# 8_-Interface_RS485.net
KiCad netlist of a schematic drawn in Altium Designer
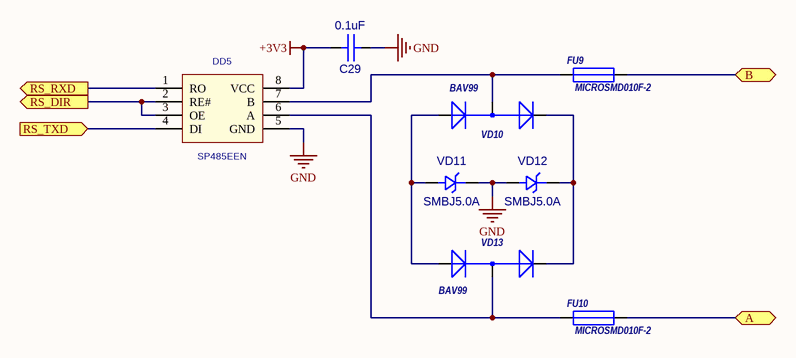
[diagram p0: [8]-Interface_RS485.SchDoc]

(export (version "E")
  (design (tool "Eeschema 10.0.6"))
  (components
    (comp (ref "C29")
      (value "0.1uF")
      (footprint "CC0603")
      (description "CC0603")
      (libsource (lib "gprs_modem_2") (part "CC0603"))
    )
    (comp (ref "DD5")
      (value "SP485EEN")
      (footprint "SO-8")
      (description "SP485")
      (libsource (lib "gprs_modem_2") (part "SP485"))
    )
    (comp (ref "FU9")
      (value "MICROSMD010F-2")
      (footprint "RC1210")
      (description "MICROSMD")
      (libsource (lib "gprs_modem_2") (part "MICROSMD"))
    )
    (comp (ref "FU10")
      (value "MICROSMD010F-2")
      (footprint "RC1210")
      (description "MICROSMD")
      (libsource (lib "gprs_modem_2") (part "MICROSMD"))
    )
    (comp (ref "VD10")
      (value "BAV99")
      (footprint "SOT-23(GSD)")
      (description "1.0 Ampere General Purpose Rectifier")
      (libsource (lib "gprs_modem_2") (part "BAV99"))
    )
    (comp (ref "VD11")
      (value "SMBJ5.0A")
      (footprint "SMB")
      (description "SMBJ")
      (libsource (lib "gprs_modem_2") (part "SMBJ"))
    )
    (comp (ref "VD12")
      (value "SMBJ5.0A")
      (footprint "SMB")
      (description "SMBJ")
      (libsource (lib "gprs_modem_2") (part "SMBJ"))
    )
    (comp (ref "VD13")
      (value "BAV99")
      (footprint "SOT-23(GSD)")
      (description "1.0 Ampere General Purpose Rectifier")
      (libsource (lib "gprs_modem_2") (part "BAV99"))
    )
  )
  (nets
    (net (code "1") (name "+3V3") (class "Default")
      (node (ref "C29") (pin "2") (pinfunction "B_2") (pintype "passive"))
      (node (ref "DD5") (pin "8") (pinfunction "VCC_8") (pintype "passive"))
    )
    (net (code "2") (name "/A") (class "Default") (node (ref "FU10") (pin "2") (pintype "passive")))
    (net (code "3") (name "/B") (class "Default") (node (ref "FU9") (pin "2") (pintype "passive")))
    (net (code "4") (name "/RS_DIR") (class "Default")
      (node (ref "DD5") (pin "2") (pinfunction "RE#_2") (pintype "passive"))
      (node (ref "DD5") (pin "3") (pinfunction "OE_3") (pintype "passive"))
    )
    (net (code "5") (name "/RS_RXD") (class "Default")
      (node (ref "DD5") (pin "1") (pinfunction "RO_1") (pintype "passive"))
    )
    (net (code "6") (name "/RS_TXD") (class "Default")
      (node (ref "DD5") (pin "4") (pinfunction "DI_4") (pintype "passive"))
    )
    (net (code "7") (name "GND") (class "Default")
      (node (ref "C29") (pin "1") (pinfunction "A_1") (pintype "passive"))
      (node (ref "DD5") (pin "5") (pinfunction "GND_5") (pintype "passive"))
      (node (ref "VD11") (pin "2") (pinfunction "K_2") (pintype "passive"))
      (node (ref "VD12") (pin "1") (pinfunction "A_1") (pintype "passive"))
    )
    (net (code "8") (name "Net-(DD5-A)") (class "Default")
      (node (ref "DD5") (pin "6") (pinfunction "A_6") (pintype "passive"))
      (node (ref "FU10") (pin "1") (pintype "passive"))
      (node (ref "VD13") (pin "3") (pinfunction "AK_3") (pintype "passive"))
    )
    (net (code "9") (name "Net-(DD5-B)") (class "Default")
      (node (ref "DD5") (pin "7") (pinfunction "B_7") (pintype "passive"))
      (node (ref "FU9") (pin "1") (pintype "passive"))
      (node (ref "VD10") (pin "3") (pinfunction "AK_3") (pintype "passive"))
    )
    (net (code "10") (name "Net-(VD10-A)") (class "Default")
      (node (ref "VD10") (pin "1") (pinfunction "A_1") (pintype "passive"))
      (node (ref "VD11") (pin "1") (pinfunction "A_1") (pintype "passive"))
      (node (ref "VD13") (pin "1") (pinfunction "A_1") (pintype "passive"))
    )
    (net (code "11") (name "Net-(VD10-K)") (class "Default")
      (node (ref "VD10") (pin "2") (pinfunction "K_2") (pintype "passive"))
      (node (ref "VD12") (pin "2") (pinfunction "K_2") (pintype "passive"))
      (node (ref "VD13") (pin "2") (pinfunction "K_2") (pintype "passive"))
    )
  )
)
